# 25Q80_SO.net
KiCad netlist of a schematic drawn in Altium Designer
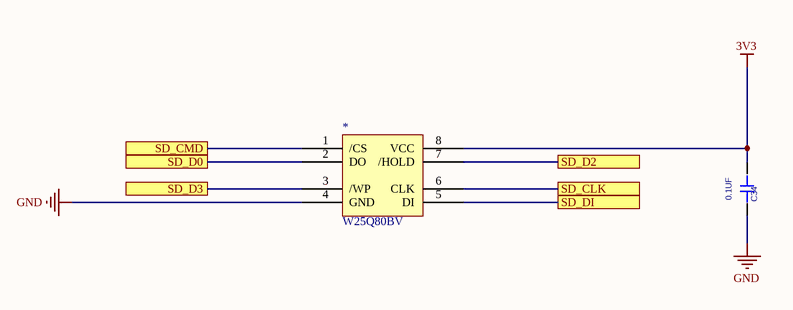
[diagram p0: 25Q80_SO.SchDoc]

(export (version "E")
  (design (tool "Eeschema 10.0.6"))
  (components
    (comp (ref "*") (value "W25Q80BV") (footprint "W25Q80BV") (libsource (lib "Inte_Car") (part "W25Q80BV")))
    (comp (ref "C34")
      (value "0.1UF")
      (footprint "CAP_0603_FIRE")
      (description "SURFACE MOUNT CAPACITOR 0.031 X 0.061 INCHES")
      (fields (field (name "Comment") "CAP_0.1UF_0603_FIRE"))
      (libsource (lib "MINI-V3") (part "CAP_0.1UF_0603_FIRE"))
    )
  )
  (nets
    (net (code "1") (name "/SD_CLK") (class "Default")
      (node (ref "*") (pin "6") (pinfunction "CLK_6") (pintype "passive"))
    )
    (net (code "2") (name "/SD_CMD") (class "Default")
      (node (ref "*") (pin "1") (pinfunction "/CS_1") (pintype "passive"))
    )
    (net (code "3") (name "/SD_D0") (class "Default")
      (node (ref "*") (pin "2") (pinfunction "DO_2") (pintype "passive"))
    )
    (net (code "4") (name "/SD_D2") (class "Default")
      (node (ref "*") (pin "7") (pinfunction "/HOLD_7") (pintype "passive"))
    )
    (net (code "5") (name "/SD_D3") (class "Default")
      (node (ref "*") (pin "3") (pinfunction "/WP_3") (pintype "passive"))
    )
    (net (code "6") (name "/SD_DI") (class "Default")
      (node (ref "*") (pin "5") (pinfunction "DI_5") (pintype "passive"))
    )
    (net (code "7") (name "3V3") (class "Default")
      (node (ref "*") (pin "8") (pinfunction "VCC_8") (pintype "passive"))
      (node (ref "C34") (pin "2") (pinfunction "2_2") (pintype "passive"))
    )
    (net (code "8") (name "GND") (class "Default")
      (node (ref "*") (pin "4") (pinfunction "GND_4") (pintype "passive"))
      (node (ref "C34") (pin "1") (pinfunction "1_1") (pintype "passive"))
    )
  )
)
